# Placa_Motor.net
KiCad netlist of a schematic drawn in EAGLE
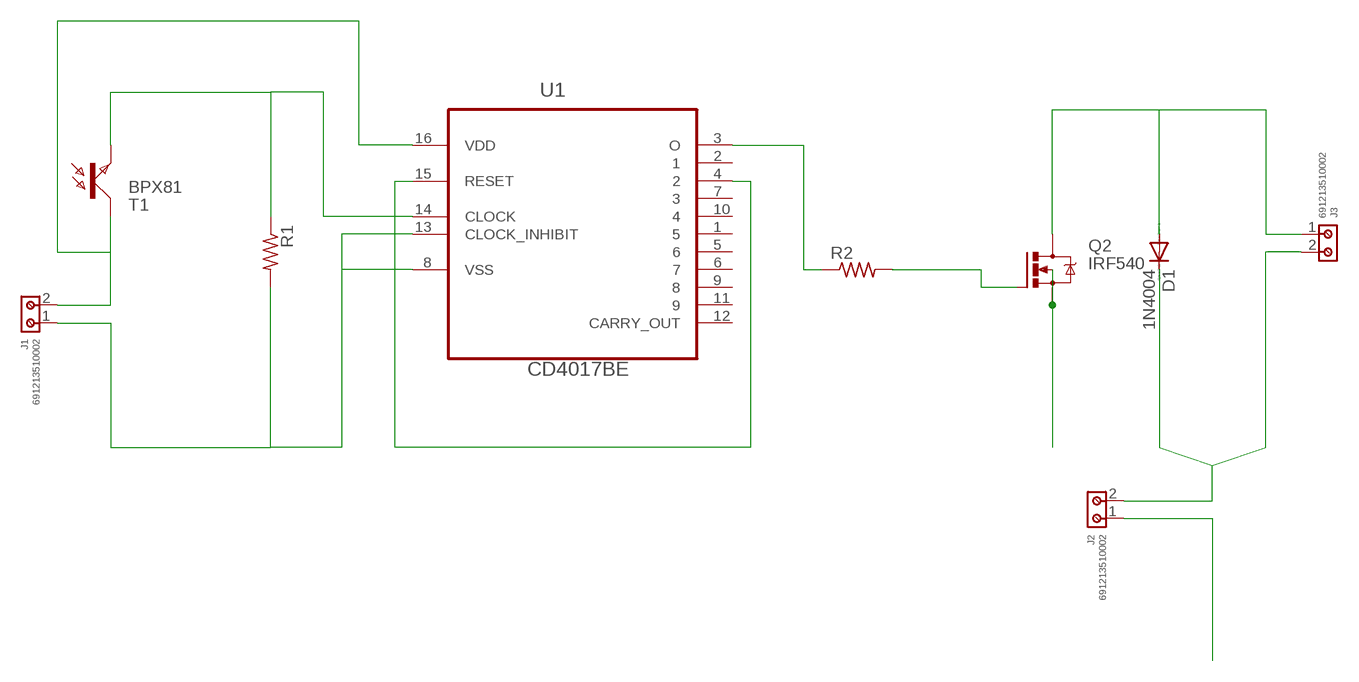
[diagram p0: schematic, sheet 1]

(export (version "E")
  (design (tool "Eeschema 10.0.6"))
  (components
    (comp (ref "D1")
      (value "1N4004")
      (footprint "eagle-import:DO41-10")
      (libsource (lib "eagle-import") (part "1N4004"))
    )
    (comp (ref "J1")
      (value "691213510002")
      (footprint "eagle-import:691213510002")
      (fields (field (name "MF") "Wurth Electronics"))
      (libsource (lib "eagle-import") (part "691213510002"))
    )
    (comp (ref "J2")
      (value "691213510002")
      (footprint "eagle-import:691213510002")
      (fields (field (name "MF") "Wurth Electronics"))
      (libsource (lib "eagle-import") (part "691213510002"))
    )
    (comp (ref "J3")
      (value "691213510002")
      (footprint "eagle-import:691213510002")
      (fields (field (name "MF") "Wurth Electronics"))
      (libsource (lib "eagle-import") (part "691213510002"))
    )
    (comp (ref "Q2")
      (value "IRF540")
      (footprint "eagle-import:TO220BV")
      (libsource (lib "eagle-import") (part "IRF540"))
    )
    (comp (ref "R1")
      (value "R-US_0309/12")
      (footprint "eagle-import:0309_12")
      (libsource (lib "eagle-import") (part "R-US_0309/12"))
    )
    (comp (ref "R2")
      (value "R-US_0309/12")
      (footprint "eagle-import:0309_12")
      (libsource (lib "eagle-import") (part "R-US_0309/12"))
    )
    (comp (ref "T1")
      (value "BPX81")
      (footprint "eagle-import:BPX81")
      (libsource (lib "eagle-import") (part "BPX81"))
    )
    (comp (ref "U1")
      (value "CD4017BE")
      (footprint "eagle-import:DIP254P762X508-16")
      (fields (field (name "MF") "Harris Corporation"))
      (libsource (lib "eagle-import") (part "CD4017BE"))
    )
  )
  (nets
    (net (code "1") (name "/GROUND") (class "Default")
      (node (ref "J1") (pin "1") (pinfunction "1_1") (pintype "passive"))
      (node (ref "J2") (pin "1") (pinfunction "1_1") (pintype "passive"))
      (node (ref "Q2") (pin "S") (pinfunction "S_S") (pintype "passive"))
      (node (ref "R1") (pin "2") (pinfunction "2_2") (pintype "passive"))
      (node (ref "U1") (pin "13") (pinfunction "CLOCK_INHIBIT_13") (pintype "input"))
      (node (ref "U1") (pin "8") (pinfunction "VSS_8") (pintype "power_in"))
    )
    (net (code "2") (name "Net-(D1-PadA)") (class "Default")
      (node (ref "D1") (pin "A") (pinfunction "A_A") (pintype "passive"))
      (node (ref "J3") (pin "1") (pinfunction "1_1") (pintype "passive"))
      (node (ref "Q2") (pin "D") (pinfunction "D_D") (pintype "passive"))
    )
    (net (code "3") (name "Net-(D1-PadC)") (class "Default")
      (node (ref "D1") (pin "C") (pinfunction "C_C") (pintype "passive"))
      (node (ref "J2") (pin "2") (pinfunction "2_2") (pintype "passive"))
      (node (ref "J3") (pin "2") (pinfunction "2_2") (pintype "passive"))
    )
    (net (code "4") (name "Net-(Q2-PadG)") (class "Default")
      (node (ref "Q2") (pin "G") (pinfunction "G_G") (pintype "passive"))
      (node (ref "R2") (pin "2") (pinfunction "2_2") (pintype "passive"))
    )
    (net (code "5") (name "Net-(U1-2)") (class "Default")
      (node (ref "U1") (pin "15") (pinfunction "RESET_15") (pintype "input"))
      (node (ref "U1") (pin "4") (pinfunction "2_4") (pintype "output"))
    )
    (net (code "6") (name "Net-(U1-CLOCK)") (class "Default")
      (node (ref "R1") (pin "1") (pinfunction "1_1") (pintype "passive"))
      (node (ref "T1") (pin "E") (pinfunction "E_E") (pintype "passive"))
      (node (ref "U1") (pin "14") (pinfunction "CLOCK_14") (pintype "input"))
    )
    (net (code "7") (name "Net-(U1-O)") (class "Default")
      (node (ref "R2") (pin "1") (pinfunction "1_1") (pintype "passive"))
      (node (ref "U1") (pin "3") (pinfunction "O_3") (pintype "output"))
    )
    (net (code "8") (name "Net-(U1-VDD)") (class "Default")
      (node (ref "J1") (pin "2") (pinfunction "2_2") (pintype "passive"))
      (node (ref "T1") (pin "C") (pinfunction "C_C") (pintype "passive"))
      (node (ref "U1") (pin "16") (pinfunction "VDD_16") (pintype "power_in"))
    )
    (net (code "9") (name "unconnected-(U1-1-Pad2)") (class "Default")
      (node (ref "U1") (pin "2") (pinfunction "1_2") (pintype "output"))
    )
    (net (code "10") (name "unconnected-(U1-3-Pad7)") (class "Default")
      (node (ref "U1") (pin "7") (pinfunction "3_7") (pintype "output"))
    )
    (net (code "11") (name "unconnected-(U1-4-Pad10)") (class "Default")
      (node (ref "U1") (pin "10") (pinfunction "4_10") (pintype "output"))
    )
    (net (code "12") (name "unconnected-(U1-5-Pad1)") (class "Default")
      (node (ref "U1") (pin "1") (pinfunction "5_1") (pintype "output"))
    )
    (net (code "13") (name "unconnected-(U1-6-Pad5)") (class "Default")
      (node (ref "U1") (pin "5") (pinfunction "6_5") (pintype "output"))
    )
    (net (code "14") (name "unconnected-(U1-7-Pad6)") (class "Default")
      (node (ref "U1") (pin "6") (pinfunction "7_6") (pintype "output"))
    )
    (net (code "15") (name "unconnected-(U1-8-Pad9)") (class "Default")
      (node (ref "U1") (pin "9") (pinfunction "8_9") (pintype "output"))
    )
    (net (code "16") (name "unconnected-(U1-9-Pad11)") (class "Default")
      (node (ref "U1") (pin "11") (pinfunction "9_11") (pintype "output"))
    )
    (net (code "17") (name "unconnected-(U1-CARRY_OUT-Pad12)") (class "Default")
      (node (ref "U1") (pin "12") (pinfunction "CARRY_OUT_12") (pintype "output"))
    )
  )
)
